# rpiz_test.net
KiCad netlist of a schematic drawn in EAGLE
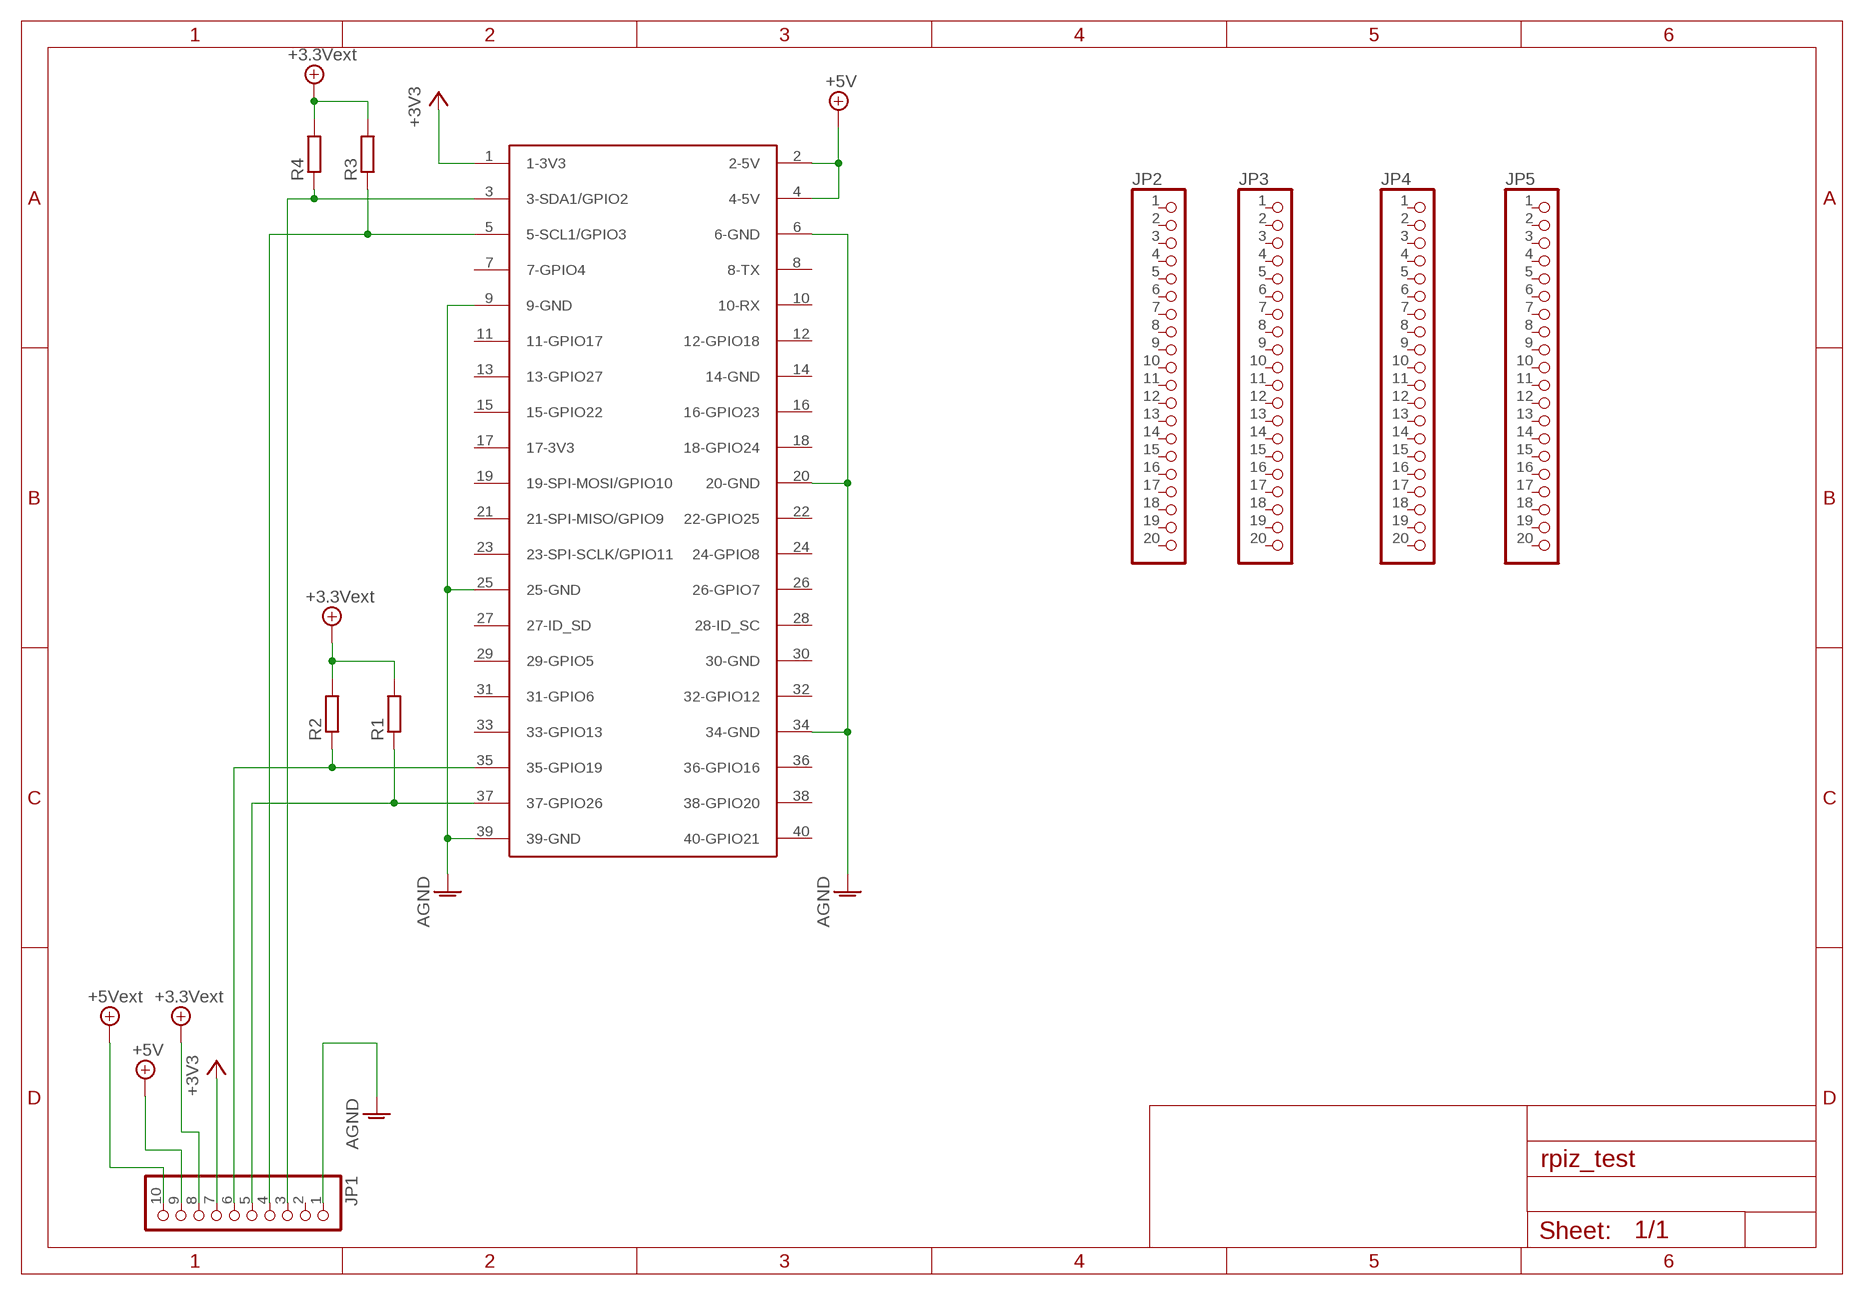
[diagram p0: schematic, sheet 1]

(export (version "E")
  (design (tool "Eeschema 10.0.6"))
  (components
    (comp (ref "JP1")
      (value "PINHD-1X10")
      (footprint "eagle-import:1X10")
      (libsource (lib "eagle-import") (part "PINHD-1X10"))
    )
    (comp (ref "JP2")
      (value "PINHD-1X20")
      (footprint "eagle-import:1X20")
      (libsource (lib "eagle-import") (part "PINHD-1X20"))
    )
    (comp (ref "JP3")
      (value "PINHD-1X20")
      (footprint "eagle-import:1X20")
      (libsource (lib "eagle-import") (part "PINHD-1X20"))
    )
    (comp (ref "JP4")
      (value "PINHD-1X20")
      (footprint "eagle-import:1X20")
      (libsource (lib "eagle-import") (part "PINHD-1X20"))
    )
    (comp (ref "JP5")
      (value "PINHD-1X20")
      (footprint "eagle-import:1X20")
      (libsource (lib "eagle-import") (part "PINHD-1X20"))
    )
    (comp (ref "R1")
      (value "R-EU_R0805")
      (footprint "eagle-import:R0805")
      (libsource (lib "eagle-import") (part "R-EU_R0805"))
    )
    (comp (ref "R2")
      (value "R-EU_R0805")
      (footprint "eagle-import:R0805")
      (libsource (lib "eagle-import") (part "R-EU_R0805"))
    )
    (comp (ref "R3")
      (value "R-EU_R0805")
      (footprint "eagle-import:R0805")
      (libsource (lib "eagle-import") (part "R-EU_R0805"))
    )
    (comp (ref "R4")
      (value "R-EU_R0805")
      (footprint "eagle-import:R0805")
      (libsource (lib "eagle-import") (part "R-EU_R0805"))
    )
    (comp (ref "U$1")
      (value "RASPBERRY-PI+PIZERO")
      (footprint "eagle-import:RASPBERRY-PI-ZERO")
      (libsource (lib "eagle-import") (part "RASPBERRY-PI+PIZERO"))
    )
  )
  (nets
    (net (code "1") (name "+3.3Vext") (class "Default")
      (node (ref "JP1") (pin "8") (pinfunction "8_8") (pintype "passive"))
      (node (ref "R1") (pin "2") (pinfunction "2_2") (pintype "passive"))
      (node (ref "R2") (pin "2") (pinfunction "2_2") (pintype "passive"))
      (node (ref "R3") (pin "2") (pinfunction "2_2") (pintype "passive"))
      (node (ref "R4") (pin "2") (pinfunction "2_2") (pintype "passive"))
    )
    (net (code "2") (name "+3V3") (class "Default")
      (node (ref "JP1") (pin "7") (pinfunction "7_7") (pintype "passive"))
      (node (ref "U$1") (pin "1") (pinfunction "1-3V3_1") (pintype "bidirectional"))
    )
    (net (code "3") (name "+5V") (class "Default")
      (node (ref "JP1") (pin "9") (pinfunction "9_9") (pintype "passive"))
      (node (ref "U$1") (pin "2") (pinfunction "2-5V_2") (pintype "bidirectional"))
      (node (ref "U$1") (pin "4") (pinfunction "4-5V_4") (pintype "bidirectional"))
    )
    (net (code "4") (name "+5Vext") (class "Default")
      (node (ref "JP1") (pin "10") (pinfunction "10_10") (pintype "passive"))
    )
    (net (code "5") (name "AGND") (class "Default")
      (node (ref "JP1") (pin "1") (pinfunction "1_1") (pintype "passive"))
      (node (ref "U$1") (pin "20") (pinfunction "20-GND_20") (pintype "bidirectional"))
      (node (ref "U$1") (pin "25") (pinfunction "25-GND_25") (pintype "bidirectional"))
      (node (ref "U$1") (pin "34") (pinfunction "34-GND_34") (pintype "bidirectional"))
      (node (ref "U$1") (pin "39") (pinfunction "39-GND_39") (pintype "bidirectional"))
      (node (ref "U$1") (pin "6") (pinfunction "6-GND_6") (pintype "bidirectional"))
      (node (ref "U$1") (pin "9") (pinfunction "9-GND_9") (pintype "bidirectional"))
    )
    (net (code "6") (name "Net-(U$1-3-SDA1{slash}GPIO2)") (class "Default")
      (node (ref "JP1") (pin "3") (pinfunction "3_3") (pintype "passive"))
      (node (ref "R4") (pin "1") (pinfunction "1_1") (pintype "passive"))
      (node (ref "U$1") (pin "3") (pinfunction "3-SDA1/GPIO2_3") (pintype "bidirectional"))
    )
    (net (code "7") (name "Net-(U$1-5-SCL1{slash}GPIO3)") (class "Default")
      (node (ref "JP1") (pin "4") (pinfunction "4_4") (pintype "passive"))
      (node (ref "R3") (pin "1") (pinfunction "1_1") (pintype "passive"))
      (node (ref "U$1") (pin "5") (pinfunction "5-SCL1/GPIO3_5") (pintype "bidirectional"))
    )
    (net (code "8") (name "Net-(U$1-35-GPIO19)") (class "Default")
      (node (ref "JP1") (pin "6") (pinfunction "6_6") (pintype "passive"))
      (node (ref "R2") (pin "1") (pinfunction "1_1") (pintype "passive"))
      (node (ref "U$1") (pin "35") (pinfunction "35-GPIO19_35") (pintype "bidirectional"))
    )
    (net (code "9") (name "Net-(U$1-37-GPIO26)") (class "Default")
      (node (ref "JP1") (pin "5") (pinfunction "5_5") (pintype "passive"))
      (node (ref "R1") (pin "1") (pinfunction "1_1") (pintype "passive"))
      (node (ref "U$1") (pin "37") (pinfunction "37-GPIO26_37") (pintype "bidirectional"))
    )
    (net (code "10") (name "unconnected-(JP1-Pad2)") (class "Default")
      (node (ref "JP1") (pin "2") (pinfunction "2_2") (pintype "passive"))
    )
    (net (code "11") (name "unconnected-(JP2-Pad1)") (class "Default")
      (node (ref "JP2") (pin "1") (pinfunction "1_1") (pintype "passive"))
    )
    (net (code "12") (name "unconnected-(JP2-Pad2)") (class "Default")
      (node (ref "JP2") (pin "2") (pinfunction "2_2") (pintype "passive"))
    )
    (net (code "13") (name "unconnected-(JP2-Pad3)") (class "Default")
      (node (ref "JP2") (pin "3") (pinfunction "3_3") (pintype "passive"))
    )
    (net (code "14") (name "unconnected-(JP2-Pad4)") (class "Default")
      (node (ref "JP2") (pin "4") (pinfunction "4_4") (pintype "passive"))
    )
    (net (code "15") (name "unconnected-(JP2-Pad5)") (class "Default")
      (node (ref "JP2") (pin "5") (pinfunction "5_5") (pintype "passive"))
    )
    (net (code "16") (name "unconnected-(JP2-Pad6)") (class "Default")
      (node (ref "JP2") (pin "6") (pinfunction "6_6") (pintype "passive"))
    )
    (net (code "17") (name "unconnected-(JP2-Pad7)") (class "Default")
      (node (ref "JP2") (pin "7") (pinfunction "7_7") (pintype "passive"))
    )
    (net (code "18") (name "unconnected-(JP2-Pad8)") (class "Default")
      (node (ref "JP2") (pin "8") (pinfunction "8_8") (pintype "passive"))
    )
    (net (code "19") (name "unconnected-(JP2-Pad9)") (class "Default")
      (node (ref "JP2") (pin "9") (pinfunction "9_9") (pintype "passive"))
    )
    (net (code "20") (name "unconnected-(JP2-Pad10)") (class "Default")
      (node (ref "JP2") (pin "10") (pinfunction "10_10") (pintype "passive"))
    )
    (net (code "21") (name "unconnected-(JP2-Pad11)") (class "Default")
      (node (ref "JP2") (pin "11") (pinfunction "11_11") (pintype "passive"))
    )
    (net (code "22") (name "unconnected-(JP2-Pad12)") (class "Default")
      (node (ref "JP2") (pin "12") (pinfunction "12_12") (pintype "passive"))
    )
    (net (code "23") (name "unconnected-(JP2-Pad13)") (class "Default")
      (node (ref "JP2") (pin "13") (pinfunction "13_13") (pintype "passive"))
    )
    (net (code "24") (name "unconnected-(JP2-Pad14)") (class "Default")
      (node (ref "JP2") (pin "14") (pinfunction "14_14") (pintype "passive"))
    )
    (net (code "25") (name "unconnected-(JP2-Pad15)") (class "Default")
      (node (ref "JP2") (pin "15") (pinfunction "15_15") (pintype "passive"))
    )
    (net (code "26") (name "unconnected-(JP2-Pad16)") (class "Default")
      (node (ref "JP2") (pin "16") (pinfunction "16_16") (pintype "passive"))
    )
    (net (code "27") (name "unconnected-(JP2-Pad17)") (class "Default")
      (node (ref "JP2") (pin "17") (pinfunction "17_17") (pintype "passive"))
    )
    (net (code "28") (name "unconnected-(JP2-Pad18)") (class "Default")
      (node (ref "JP2") (pin "18") (pinfunction "18_18") (pintype "passive"))
    )
    (net (code "29") (name "unconnected-(JP2-Pad19)") (class "Default")
      (node (ref "JP2") (pin "19") (pinfunction "19_19") (pintype "passive"))
    )
    (net (code "30") (name "unconnected-(JP2-Pad20)") (class "Default")
      (node (ref "JP2") (pin "20") (pinfunction "20_20") (pintype "passive"))
    )
    (net (code "31") (name "unconnected-(JP3-Pad1)") (class "Default")
      (node (ref "JP3") (pin "1") (pinfunction "1_1") (pintype "passive"))
    )
    (net (code "32") (name "unconnected-(JP3-Pad2)") (class "Default")
      (node (ref "JP3") (pin "2") (pinfunction "2_2") (pintype "passive"))
    )
    (net (code "33") (name "unconnected-(JP3-Pad3)") (class "Default")
      (node (ref "JP3") (pin "3") (pinfunction "3_3") (pintype "passive"))
    )
    (net (code "34") (name "unconnected-(JP3-Pad4)") (class "Default")
      (node (ref "JP3") (pin "4") (pinfunction "4_4") (pintype "passive"))
    )
    (net (code "35") (name "unconnected-(JP3-Pad5)") (class "Default")
      (node (ref "JP3") (pin "5") (pinfunction "5_5") (pintype "passive"))
    )
    (net (code "36") (name "unconnected-(JP3-Pad6)") (class "Default")
      (node (ref "JP3") (pin "6") (pinfunction "6_6") (pintype "passive"))
    )
    (net (code "37") (name "unconnected-(JP3-Pad7)") (class "Default")
      (node (ref "JP3") (pin "7") (pinfunction "7_7") (pintype "passive"))
    )
    (net (code "38") (name "unconnected-(JP3-Pad8)") (class "Default")
      (node (ref "JP3") (pin "8") (pinfunction "8_8") (pintype "passive"))
    )
    (net (code "39") (name "unconnected-(JP3-Pad9)") (class "Default")
      (node (ref "JP3") (pin "9") (pinfunction "9_9") (pintype "passive"))
    )
    (net (code "40") (name "unconnected-(JP3-Pad10)") (class "Default")
      (node (ref "JP3") (pin "10") (pinfunction "10_10") (pintype "passive"))
    )
    (net (code "41") (name "unconnected-(JP3-Pad11)") (class "Default")
      (node (ref "JP3") (pin "11") (pinfunction "11_11") (pintype "passive"))
    )
    (net (code "42") (name "unconnected-(JP3-Pad12)") (class "Default")
      (node (ref "JP3") (pin "12") (pinfunction "12_12") (pintype "passive"))
    )
    (net (code "43") (name "unconnected-(JP3-Pad13)") (class "Default")
      (node (ref "JP3") (pin "13") (pinfunction "13_13") (pintype "passive"))
    )
    (net (code "44") (name "unconnected-(JP3-Pad14)") (class "Default")
      (node (ref "JP3") (pin "14") (pinfunction "14_14") (pintype "passive"))
    )
    (net (code "45") (name "unconnected-(JP3-Pad15)") (class "Default")
      (node (ref "JP3") (pin "15") (pinfunction "15_15") (pintype "passive"))
    )
    (net (code "46") (name "unconnected-(JP3-Pad16)") (class "Default")
      (node (ref "JP3") (pin "16") (pinfunction "16_16") (pintype "passive"))
    )
    (net (code "47") (name "unconnected-(JP3-Pad17)") (class "Default")
      (node (ref "JP3") (pin "17") (pinfunction "17_17") (pintype "passive"))
    )
    (net (code "48") (name "unconnected-(JP3-Pad18)") (class "Default")
      (node (ref "JP3") (pin "18") (pinfunction "18_18") (pintype "passive"))
    )
    (net (code "49") (name "unconnected-(JP3-Pad19)") (class "Default")
      (node (ref "JP3") (pin "19") (pinfunction "19_19") (pintype "passive"))
    )
    (net (code "50") (name "unconnected-(JP3-Pad20)") (class "Default")
      (node (ref "JP3") (pin "20") (pinfunction "20_20") (pintype "passive"))
    )
    (net (code "51") (name "unconnected-(JP4-Pad1)") (class "Default")
      (node (ref "JP4") (pin "1") (pinfunction "1_1") (pintype "passive"))
    )
    (net (code "52") (name "unconnected-(JP4-Pad2)") (class "Default")
      (node (ref "JP4") (pin "2") (pinfunction "2_2") (pintype "passive"))
    )
    (net (code "53") (name "unconnected-(JP4-Pad3)") (class "Default")
      (node (ref "JP4") (pin "3") (pinfunction "3_3") (pintype "passive"))
    )
    (net (code "54") (name "unconnected-(JP4-Pad4)") (class "Default")
      (node (ref "JP4") (pin "4") (pinfunction "4_4") (pintype "passive"))
    )
    (net (code "55") (name "unconnected-(JP4-Pad5)") (class "Default")
      (node (ref "JP4") (pin "5") (pinfunction "5_5") (pintype "passive"))
    )
    (net (code "56") (name "unconnected-(JP4-Pad6)") (class "Default")
      (node (ref "JP4") (pin "6") (pinfunction "6_6") (pintype "passive"))
    )
    (net (code "57") (name "unconnected-(JP4-Pad7)") (class "Default")
      (node (ref "JP4") (pin "7") (pinfunction "7_7") (pintype "passive"))
    )
    (net (code "58") (name "unconnected-(JP4-Pad8)") (class "Default")
      (node (ref "JP4") (pin "8") (pinfunction "8_8") (pintype "passive"))
    )
    (net (code "59") (name "unconnected-(JP4-Pad9)") (class "Default")
      (node (ref "JP4") (pin "9") (pinfunction "9_9") (pintype "passive"))
    )
    (net (code "60") (name "unconnected-(JP4-Pad10)") (class "Default")
      (node (ref "JP4") (pin "10") (pinfunction "10_10") (pintype "passive"))
    )
    (net (code "61") (name "unconnected-(JP4-Pad11)") (class "Default")
      (node (ref "JP4") (pin "11") (pinfunction "11_11") (pintype "passive"))
    )
    (net (code "62") (name "unconnected-(JP4-Pad12)") (class "Default")
      (node (ref "JP4") (pin "12") (pinfunction "12_12") (pintype "passive"))
    )
    (net (code "63") (name "unconnected-(JP4-Pad13)") (class "Default")
      (node (ref "JP4") (pin "13") (pinfunction "13_13") (pintype "passive"))
    )
    (net (code "64") (name "unconnected-(JP4-Pad14)") (class "Default")
      (node (ref "JP4") (pin "14") (pinfunction "14_14") (pintype "passive"))
    )
    (net (code "65") (name "unconnected-(JP4-Pad15)") (class "Default")
      (node (ref "JP4") (pin "15") (pinfunction "15_15") (pintype "passive"))
    )
    (net (code "66") (name "unconnected-(JP4-Pad16)") (class "Default")
      (node (ref "JP4") (pin "16") (pinfunction "16_16") (pintype "passive"))
    )
    (net (code "67") (name "unconnected-(JP4-Pad17)") (class "Default")
      (node (ref "JP4") (pin "17") (pinfunction "17_17") (pintype "passive"))
    )
    (net (code "68") (name "unconnected-(JP4-Pad18)") (class "Default")
      (node (ref "JP4") (pin "18") (pinfunction "18_18") (pintype "passive"))
    )
    (net (code "69") (name "unconnected-(JP4-Pad19)") (class "Default")
      (node (ref "JP4") (pin "19") (pinfunction "19_19") (pintype "passive"))
    )
    (net (code "70") (name "unconnected-(JP4-Pad20)") (class "Default")
      (node (ref "JP4") (pin "20") (pinfunction "20_20") (pintype "passive"))
    )
    (net (code "71") (name "unconnected-(JP5-Pad1)") (class "Default")
      (node (ref "JP5") (pin "1") (pinfunction "1_1") (pintype "passive"))
    )
    (net (code "72") (name "unconnected-(JP5-Pad2)") (class "Default")
      (node (ref "JP5") (pin "2") (pinfunction "2_2") (pintype "passive"))
    )
    (net (code "73") (name "unconnected-(JP5-Pad3)") (class "Default")
      (node (ref "JP5") (pin "3") (pinfunction "3_3") (pintype "passive"))
    )
    (net (code "74") (name "unconnected-(JP5-Pad4)") (class "Default")
      (node (ref "JP5") (pin "4") (pinfunction "4_4") (pintype "passive"))
    )
    (net (code "75") (name "unconnected-(JP5-Pad5)") (class "Default")
      (node (ref "JP5") (pin "5") (pinfunction "5_5") (pintype "passive"))
    )
    (net (code "76") (name "unconnected-(JP5-Pad6)") (class "Default")
      (node (ref "JP5") (pin "6") (pinfunction "6_6") (pintype "passive"))
    )
    (net (code "77") (name "unconnected-(JP5-Pad7)") (class "Default")
      (node (ref "JP5") (pin "7") (pinfunction "7_7") (pintype "passive"))
    )
    (net (code "78") (name "unconnected-(JP5-Pad8)") (class "Default")
      (node (ref "JP5") (pin "8") (pinfunction "8_8") (pintype "passive"))
    )
    (net (code "79") (name "unconnected-(JP5-Pad9)") (class "Default")
      (node (ref "JP5") (pin "9") (pinfunction "9_9") (pintype "passive"))
    )
    (net (code "80") (name "unconnected-(JP5-Pad10)") (class "Default")
      (node (ref "JP5") (pin "10") (pinfunction "10_10") (pintype "passive"))
    )
    (net (code "81") (name "unconnected-(JP5-Pad11)") (class "Default")
      (node (ref "JP5") (pin "11") (pinfunction "11_11") (pintype "passive"))
    )
    (net (code "82") (name "unconnected-(JP5-Pad12)") (class "Default")
      (node (ref "JP5") (pin "12") (pinfunction "12_12") (pintype "passive"))
    )
    (net (code "83") (name "unconnected-(JP5-Pad13)") (class "Default")
      (node (ref "JP5") (pin "13") (pinfunction "13_13") (pintype "passive"))
    )
    (net (code "84") (name "unconnected-(JP5-Pad14)") (class "Default")
      (node (ref "JP5") (pin "14") (pinfunction "14_14") (pintype "passive"))
    )
    (net (code "85") (name "unconnected-(JP5-Pad15)") (class "Default")
      (node (ref "JP5") (pin "15") (pinfunction "15_15") (pintype "passive"))
    )
    (net (code "86") (name "unconnected-(JP5-Pad16)") (class "Default")
      (node (ref "JP5") (pin "16") (pinfunction "16_16") (pintype "passive"))
    )
    (net (code "87") (name "unconnected-(JP5-Pad17)") (class "Default")
      (node (ref "JP5") (pin "17") (pinfunction "17_17") (pintype "passive"))
    )
    (net (code "88") (name "unconnected-(JP5-Pad18)") (class "Default")
      (node (ref "JP5") (pin "18") (pinfunction "18_18") (pintype "passive"))
    )
    (net (code "89") (name "unconnected-(JP5-Pad19)") (class "Default")
      (node (ref "JP5") (pin "19") (pinfunction "19_19") (pintype "passive"))
    )
    (net (code "90") (name "unconnected-(JP5-Pad20)") (class "Default")
      (node (ref "JP5") (pin "20") (pinfunction "20_20") (pintype "passive"))
    )
    (net (code "91") (name "unconnected-(U$1-7-GPIO4-Pad7)") (class "Default")
      (node (ref "U$1") (pin "7") (pinfunction "7-GPIO4_7") (pintype "bidirectional"))
    )
    (net (code "92") (name "unconnected-(U$1-8-TX-Pad8)") (class "Default")
      (node (ref "U$1") (pin "8") (pinfunction "8-TX_8") (pintype "bidirectional"))
    )
    (net (code "93") (name "unconnected-(U$1-10-RX-Pad10)") (class "Default")
      (node (ref "U$1") (pin "10") (pinfunction "10-RX_10") (pintype "bidirectional"))
    )
    (net (code "94") (name "unconnected-(U$1-11-GPIO17-Pad11)") (class "Default")
      (node (ref "U$1") (pin "11") (pinfunction "11-GPIO17_11") (pintype "bidirectional"))
    )
    (net (code "95") (name "unconnected-(U$1-12-GPIO18-Pad12)") (class "Default")
      (node (ref "U$1") (pin "12") (pinfunction "12-GPIO18_12") (pintype "bidirectional"))
    )
    (net (code "96") (name "unconnected-(U$1-13-GPIO27-Pad13)") (class "Default")
      (node (ref "U$1") (pin "13") (pinfunction "13-GPIO27_13") (pintype "bidirectional"))
    )
    (net (code "97") (name "unconnected-(U$1-14-GND-Pad14)") (class "Default")
      (node (ref "U$1") (pin "14") (pinfunction "14-GND_14") (pintype "bidirectional"))
    )
    (net (code "98") (name "unconnected-(U$1-15-GPIO22-Pad15)") (class "Default")
      (node (ref "U$1") (pin "15") (pinfunction "15-GPIO22_15") (pintype "bidirectional"))
    )
    (net (code "99") (name "unconnected-(U$1-16-GPIO23-Pad16)") (class "Default")
      (node (ref "U$1") (pin "16") (pinfunction "16-GPIO23_16") (pintype "bidirectional"))
    )
    (net (code "100") (name "unconnected-(U$1-17-3V3-Pad17)") (class "Default")
      (node (ref "U$1") (pin "17") (pinfunction "17-3V3_17") (pintype "bidirectional"))
    )
    (net (code "101") (name "unconnected-(U$1-18-GPIO24-Pad18)") (class "Default")
      (node (ref "U$1") (pin "18") (pinfunction "18-GPIO24_18") (pintype "bidirectional"))
    )
    (net (code "102") (name "unconnected-(U$1-19-SPI-MOSI{slash}GPIO10-Pad19)") (class "Default")
      (node (ref "U$1") (pin "19") (pinfunction "19-SPI-MOSI/GPIO10_19") (pintype "bidirectional"))
    )
    (net (code "103") (name "unconnected-(U$1-21-SPI-MISO{slash}GPIO9-Pad21)") (class "Default")
      (node (ref "U$1") (pin "21") (pinfunction "21-SPI-MISO/GPIO9_21") (pintype "bidirectional"))
    )
    (net (code "104") (name "unconnected-(U$1-22-GPIO25-Pad22)") (class "Default")
      (node (ref "U$1") (pin "22") (pinfunction "22-GPIO25_22") (pintype "bidirectional"))
    )
    (net (code "105") (name "unconnected-(U$1-23-SPI-SCLK{slash}GPIO11-Pad23)") (class "Default")
      (node (ref "U$1") (pin "23") (pinfunction "23-SPI-SCLK/GPIO11_23") (pintype "bidirectional"))
    )
    (net (code "106") (name "unconnected-(U$1-24-GPIO8-Pad24)") (class "Default")
      (node (ref "U$1") (pin "24") (pinfunction "24-GPIO8_24") (pintype "bidirectional"))
    )
    (net (code "107") (name "unconnected-(U$1-26-GPIO7-Pad26)") (class "Default")
      (node (ref "U$1") (pin "26") (pinfunction "26-GPIO7_26") (pintype "bidirectional"))
    )
    (net (code "108") (name "unconnected-(U$1-27-ID_SD-Pad27)") (class "Default")
      (node (ref "U$1") (pin "27") (pinfunction "27-ID_SD_27") (pintype "bidirectional"))
    )
    (net (code "109") (name "unconnected-(U$1-28-ID_SC-Pad28)") (class "Default")
      (node (ref "U$1") (pin "28") (pinfunction "28-ID_SC_28") (pintype "bidirectional"))
    )
    (net (code "110") (name "unconnected-(U$1-29-GPIO5-Pad29)") (class "Default")
      (node (ref "U$1") (pin "29") (pinfunction "29-GPIO5_29") (pintype "bidirectional"))
    )
    (net (code "111") (name "unconnected-(U$1-30-GND-Pad30)") (class "Default")
      (node (ref "U$1") (pin "30") (pinfunction "30-GND_30") (pintype "bidirectional"))
    )
    (net (code "112") (name "unconnected-(U$1-31-GPIO6-Pad31)") (class "Default")
      (node (ref "U$1") (pin "31") (pinfunction "31-GPIO6_31") (pintype "bidirectional"))
    )
    (net (code "113") (name "unconnected-(U$1-32-GPIO12-Pad32)") (class "Default")
      (node (ref "U$1") (pin "32") (pinfunction "32-GPIO12_32") (pintype "bidirectional"))
    )
    (net (code "114") (name "unconnected-(U$1-33-GPIO13-Pad33)") (class "Default")
      (node (ref "U$1") (pin "33") (pinfunction "33-GPIO13_33") (pintype "bidirectional"))
    )
    (net (code "115") (name "unconnected-(U$1-36-GPIO16-Pad36)") (class "Default")
      (node (ref "U$1") (pin "36") (pinfunction "36-GPIO16_36") (pintype "bidirectional"))
    )
    (net (code "116") (name "unconnected-(U$1-38-GPIO20-Pad38)") (class "Default")
      (node (ref "U$1") (pin "38") (pinfunction "38-GPIO20_38") (pintype "bidirectional"))
    )
    (net (code "117") (name "unconnected-(U$1-40-GPIO21-Pad40)") (class "Default")
      (node (ref "U$1") (pin "40") (pinfunction "40-GPIO21_40") (pintype "bidirectional"))
    )
  )
)
